# FPGA_PWR.net
KiCad netlist of a schematic drawn in Altium Designer
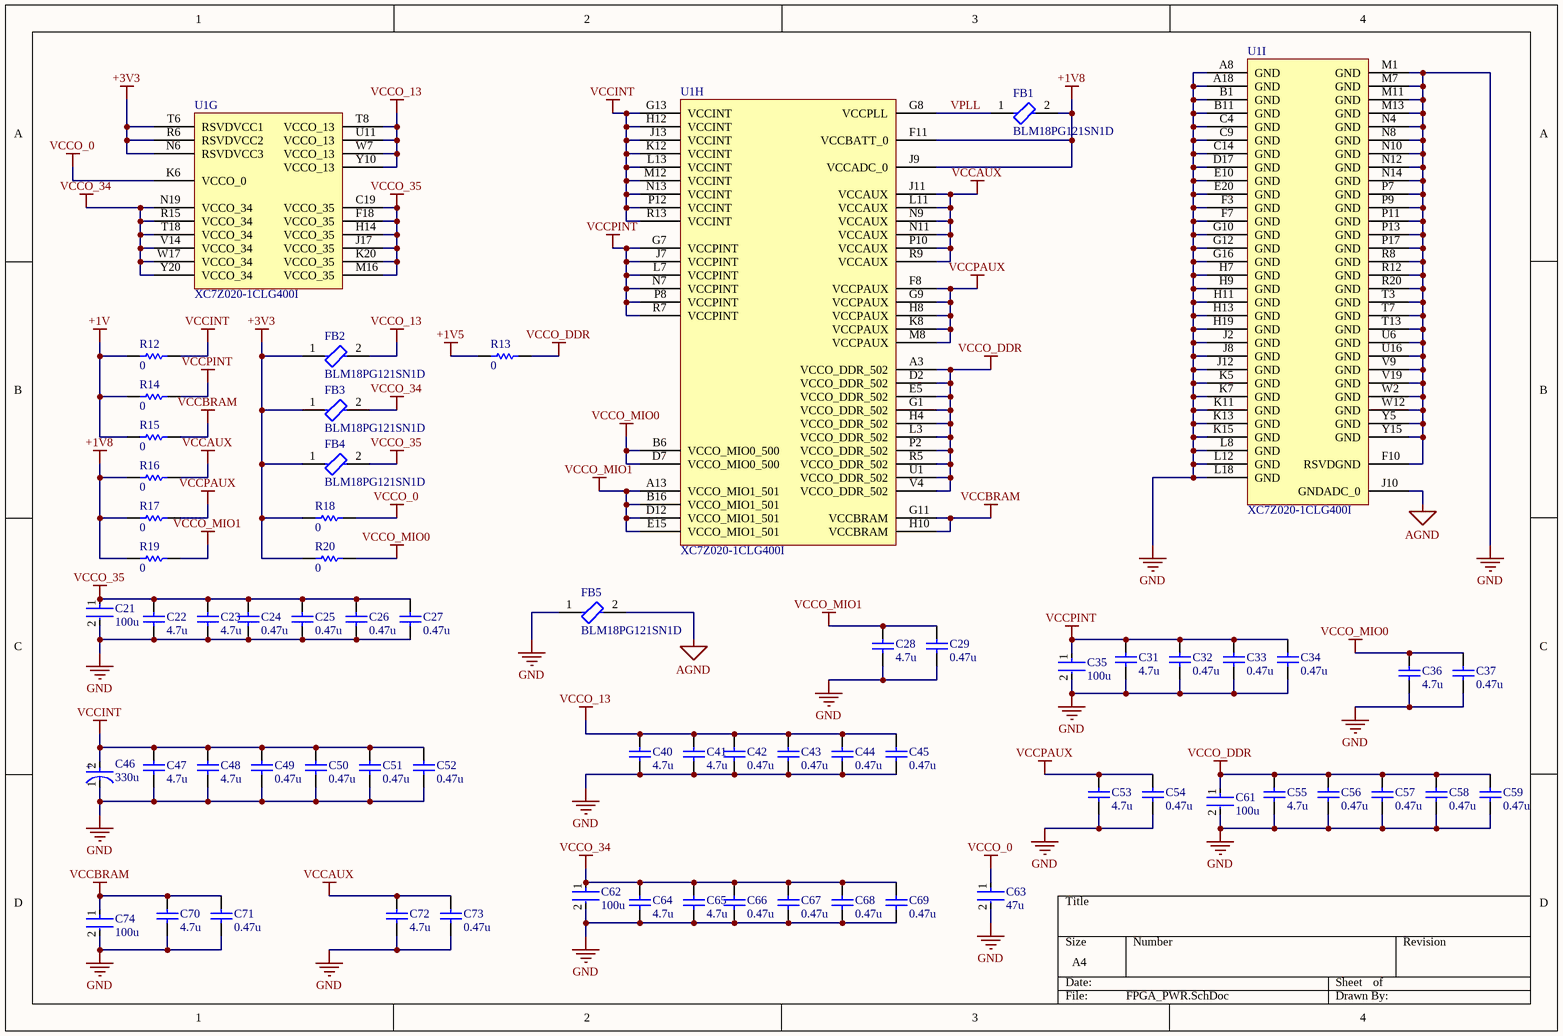
[diagram p0: FPGA_PWR.SchDoc]

(export (version "E")
  (design (tool "Eeschema 10.0.6"))
  (components
    (comp (ref "C21")
      (value "100u")
      (footprint "FP-GRM32E-0_3-0_2-MFG")
      (description "Chip Multilayer Ceramic Capacitors for General Purpose, 1210, 100uF, X7U, +22%/-56%, 20%, 4V")
      (fields (field (name "TOLERANCE") "20%"))
      (libsource (lib "Altium Content Vault") (part "02cd4be3c70576c341d710602a673aa"))
    )
    (comp (ref "C22")
      (value "4.7u")
      (footprint "CAPC2013X135X45LL10T25")
      (fields (field (name "MANUFACTURER") "Murata") (field (name "PART NUMBER") "GRM21BR71A475KA73L"))
      (libsource (lib "Altium Content Vault") (part "CAP"))
    )
    (comp (ref "C23")
      (value "4.7u")
      (footprint "CAPC2013X135X45LL10T25")
      (fields (field (name "MANUFACTURER") "Murata") (field (name "PART NUMBER") "GRM21BR71A475KA73L"))
      (libsource (lib "Altium Content Vault") (part "CAP"))
    )
    (comp (ref "C24")
      (value "0.47u")
      (footprint "CAPC1608X90X35LL10T15")
      (fields (field (name "PART NUMBER") "GRM188R70J474KA01D") (field (name "MANUFACTURER") "Murata"))
      (libsource (lib "Altium Content Vault") (part "CAP"))
    )
    (comp (ref "C25")
      (value "0.47u")
      (footprint "CAPC1608X90X35LL10T15")
      (fields (field (name "PART NUMBER") "GRM188R70J474KA01D") (field (name "MANUFACTURER") "Murata"))
      (libsource (lib "Altium Content Vault") (part "CAP"))
    )
    (comp (ref "C26")
      (value "0.47u")
      (footprint "CAPC1608X90X35LL10T15")
      (fields (field (name "PART NUMBER") "GRM188R70J474KA01D") (field (name "MANUFACTURER") "Murata"))
      (libsource (lib "Altium Content Vault") (part "CAP"))
    )
    (comp (ref "C27")
      (value "0.47u")
      (footprint "CAPC1608X90X35LL10T15")
      (fields (field (name "PART NUMBER") "GRM188R70J474KA01D") (field (name "MANUFACTURER") "Murata"))
      (libsource (lib "Altium Content Vault") (part "CAP"))
    )
    (comp (ref "C28")
      (value "4.7u")
      (footprint "CAPC2013X135X45LL10T25")
      (fields (field (name "MANUFACTURER") "Murata") (field (name "PART NUMBER") "GRM21BR71A475KA73L"))
      (libsource (lib "Altium Content Vault") (part "CAP"))
    )
    (comp (ref "C29")
      (value "0.47u")
      (footprint "CAPC1608X90X35LL10T15")
      (fields (field (name "PART NUMBER") "GRM188R70J474KA01D") (field (name "MANUFACTURER") "Murata"))
      (libsource (lib "Altium Content Vault") (part "CAP"))
    )
    (comp (ref "C31")
      (value "4.7u")
      (footprint "CAPC2013X135X45LL10T25")
      (fields (field (name "MANUFACTURER") "Murata") (field (name "PART NUMBER") "GRM21BR71A475KA73L"))
      (libsource (lib "Altium Content Vault") (part "CAP"))
    )
    (comp (ref "C32")
      (value "0.47u")
      (footprint "CAPC1608X90X35LL10T15")
      (fields (field (name "PART NUMBER") "GRM188R70J474KA01D") (field (name "MANUFACTURER") "Murata"))
      (libsource (lib "Altium Content Vault") (part "CAP"))
    )
    (comp (ref "C33")
      (value "0.47u")
      (footprint "CAPC1608X90X35LL10T15")
      (fields (field (name "PART NUMBER") "GRM188R70J474KA01D") (field (name "MANUFACTURER") "Murata"))
      (libsource (lib "Altium Content Vault") (part "CAP"))
    )
    (comp (ref "C34")
      (value "0.47u")
      (footprint "CAPC1608X90X35LL10T15")
      (fields (field (name "PART NUMBER") "GRM188R70J474KA01D") (field (name "MANUFACTURER") "Murata"))
      (libsource (lib "Altium Content Vault") (part "CAP"))
    )
    (comp (ref "C35")
      (value "100u")
      (footprint "FP-GRM32E-0_3-0_2-MFG")
      (description "Chip Multilayer Ceramic Capacitors for General Purpose, 1210, 100uF, X7U, +22%/-56%, 20%, 4V")
      (fields (field (name "TOLERANCE") "20%"))
      (libsource (lib "Altium Content Vault") (part "02cd4be3c70576c341d710602a673aa"))
    )
    (comp (ref "C36")
      (value "4.7u")
      (footprint "CAPC2013X135X45LL10T25")
      (fields (field (name "MANUFACTURER") "Murata") (field (name "PART NUMBER") "GRM21BR71A475KA73L"))
      (libsource (lib "Altium Content Vault") (part "CAP"))
    )
    (comp (ref "C37")
      (value "0.47u")
      (footprint "CAPC1608X90X35LL10T15")
      (fields (field (name "PART NUMBER") "GRM188R70J474KA01D") (field (name "MANUFACTURER") "Murata"))
      (libsource (lib "Altium Content Vault") (part "CAP"))
    )
    (comp (ref "C40")
      (value "4.7u")
      (footprint "CAPC2013X135X45LL10T25")
      (fields (field (name "MANUFACTURER") "Murata") (field (name "PART NUMBER") "GRM21BR71A475KA73L"))
      (libsource (lib "Altium Content Vault") (part "CAP"))
    )
    (comp (ref "C41")
      (value "4.7u")
      (footprint "CAPC2013X135X45LL10T25")
      (fields (field (name "MANUFACTURER") "Murata") (field (name "PART NUMBER") "GRM21BR71A475KA73L"))
      (libsource (lib "Altium Content Vault") (part "CAP"))
    )
    (comp (ref "C42")
      (value "0.47u")
      (footprint "CAPC1608X90X35LL10T15")
      (fields (field (name "PART NUMBER") "GRM188R70J474KA01D") (field (name "MANUFACTURER") "Murata"))
      (libsource (lib "Altium Content Vault") (part "CAP"))
    )
    (comp (ref "C43")
      (value "0.47u")
      (footprint "CAPC1608X90X35LL10T15")
      (fields (field (name "PART NUMBER") "GRM188R70J474KA01D") (field (name "MANUFACTURER") "Murata"))
      (libsource (lib "Altium Content Vault") (part "CAP"))
    )
    (comp (ref "C44")
      (value "0.47u")
      (footprint "CAPC1608X90X35LL10T15")
      (fields (field (name "PART NUMBER") "GRM188R70J474KA01D") (field (name "MANUFACTURER") "Murata"))
      (libsource (lib "Altium Content Vault") (part "CAP"))
    )
    (comp (ref "C45")
      (value "0.47u")
      (footprint "CAPC1608X90X35LL10T15")
      (fields (field (name "PART NUMBER") "GRM188R70J474KA01D") (field (name "MANUFACTURER") "Murata"))
      (libsource (lib "Altium Content Vault") (part "CAP"))
    )
    (comp (ref "C46")
      (value "330u")
      (footprint "FP-POSCAP-D2E-MFG")
      (description "Molded Tantalum Polymer Capacitor 330uF 20% 6.3V life 2000Hours SMD 2917")
      (fields (field (name "VOLTAGE") "6.3V") (field (name "TOLERANCE") "20%"))
      (libsource (lib "Altium Content Vault") (part "84cdeef69100fe67ea2095257d64e1a"))
    )
    (comp (ref "C47")
      (value "4.7u")
      (footprint "CAPC2013X135X45LL10T25")
      (fields (field (name "MANUFACTURER") "Murata") (field (name "PART NUMBER") "GRM21BR71A475KA73L"))
      (libsource (lib "Altium Content Vault") (part "CAP"))
    )
    (comp (ref "C48")
      (value "4.7u")
      (footprint "CAPC2013X135X45LL10T25")
      (fields (field (name "MANUFACTURER") "Murata") (field (name "PART NUMBER") "GRM21BR71A475KA73L"))
      (libsource (lib "Altium Content Vault") (part "CAP"))
    )
    (comp (ref "C49")
      (value "0.47u")
      (footprint "CAPC1608X90X35LL10T15")
      (fields (field (name "PART NUMBER") "GRM188R70J474KA01D") (field (name "MANUFACTURER") "Murata"))
      (libsource (lib "Altium Content Vault") (part "CAP"))
    )
    (comp (ref "C50")
      (value "0.47u")
      (footprint "CAPC1608X90X35LL10T15")
      (fields (field (name "PART NUMBER") "GRM188R70J474KA01D") (field (name "MANUFACTURER") "Murata"))
      (libsource (lib "Altium Content Vault") (part "CAP"))
    )
    (comp (ref "C51")
      (value "0.47u")
      (footprint "CAPC1608X90X35LL10T15")
      (fields (field (name "PART NUMBER") "GRM188R70J474KA01D") (field (name "MANUFACTURER") "Murata"))
      (libsource (lib "Altium Content Vault") (part "CAP"))
    )
    (comp (ref "C52")
      (value "0.47u")
      (footprint "CAPC1608X90X35LL10T15")
      (fields (field (name "PART NUMBER") "GRM188R70J474KA01D") (field (name "MANUFACTURER") "Murata"))
      (libsource (lib "Altium Content Vault") (part "CAP"))
    )
    (comp (ref "C53")
      (value "4.7u")
      (footprint "CAPC2013X135X45LL10T25")
      (fields (field (name "MANUFACTURER") "Murata") (field (name "PART NUMBER") "GRM21BR71A475KA73L"))
      (libsource (lib "Altium Content Vault") (part "CAP"))
    )
    (comp (ref "C54")
      (value "0.47u")
      (footprint "CAPC1608X90X35LL10T15")
      (fields (field (name "PART NUMBER") "GRM188R70J474KA01D") (field (name "MANUFACTURER") "Murata"))
      (libsource (lib "Altium Content Vault") (part "CAP"))
    )
    (comp (ref "C55")
      (value "4.7u")
      (footprint "CAPC2013X135X45LL10T25")
      (fields (field (name "MANUFACTURER") "Murata") (field (name "PART NUMBER") "GRM21BR71A475KA73L"))
      (libsource (lib "Altium Content Vault") (part "CAP"))
    )
    (comp (ref "C56")
      (value "0.47u")
      (footprint "CAPC1608X90X35LL10T15")
      (fields (field (name "PART NUMBER") "GRM188R70J474KA01D") (field (name "MANUFACTURER") "Murata"))
      (libsource (lib "Altium Content Vault") (part "CAP"))
    )
    (comp (ref "C57")
      (value "0.47u")
      (footprint "CAPC1608X90X35LL10T15")
      (fields (field (name "PART NUMBER") "GRM188R70J474KA01D") (field (name "MANUFACTURER") "Murata"))
      (libsource (lib "Altium Content Vault") (part "CAP"))
    )
    (comp (ref "C58")
      (value "0.47u")
      (footprint "CAPC1608X90X35LL10T15")
      (fields (field (name "PART NUMBER") "GRM188R70J474KA01D") (field (name "MANUFACTURER") "Murata"))
      (libsource (lib "Altium Content Vault") (part "CAP"))
    )
    (comp (ref "C59")
      (value "0.47u")
      (footprint "CAPC1608X90X35LL10T15")
      (fields (field (name "PART NUMBER") "GRM188R70J474KA01D") (field (name "MANUFACTURER") "Murata"))
      (libsource (lib "Altium Content Vault") (part "CAP"))
    )
    (comp (ref "C61")
      (value "100u")
      (footprint "FP-GRM32E-0_3-0_2-MFG")
      (description "Chip Multilayer Ceramic Capacitors for General Purpose, 1210, 100uF, X7U, +22%/-56%, 20%, 4V")
      (fields (field (name "TOLERANCE") "20%"))
      (libsource (lib "Altium Content Vault") (part "02cd4be3c70576c341d710602a673aa"))
    )
    (comp (ref "C62")
      (value "100u")
      (footprint "FP-GRM32E-0_3-0_2-MFG")
      (description "Chip Multilayer Ceramic Capacitors for General Purpose, 1210, 100uF, X7U, +22%/-56%, 20%, 4V")
      (fields (field (name "TOLERANCE") "20%"))
      (libsource (lib "Altium Content Vault") (part "02cd4be3c70576c341d710602a673aa"))
    )
    (comp (ref "C63")
      (value "47u")
      (footprint "FP-GRM32E-0_3-0_2-IPC_C")
      (description "Chip Multilayer Ceramic Capacitors for General Purpose, 1210, 47uF, X7R, 15%, 20%, 6.3V")
      (fields (field (name "TOLERANCE") "20%"))
      (libsource (lib "Altium Content Vault") (part "02cd4be3c70576c341d710602a673aa"))
    )
    (comp (ref "C64")
      (value "4.7u")
      (footprint "CAPC2013X135X45LL10T25")
      (fields (field (name "MANUFACTURER") "Murata") (field (name "PART NUMBER") "GRM21BR71A475KA73L"))
      (libsource (lib "Altium Content Vault") (part "CAP"))
    )
    (comp (ref "C65")
      (value "4.7u")
      (footprint "CAPC2013X135X45LL10T25")
      (fields (field (name "MANUFACTURER") "Murata") (field (name "PART NUMBER") "GRM21BR71A475KA73L"))
      (libsource (lib "Altium Content Vault") (part "CAP"))
    )
    (comp (ref "C66")
      (value "0.47u")
      (footprint "CAPC1608X90X35LL10T15")
      (fields (field (name "PART NUMBER") "GRM188R70J474KA01D") (field (name "MANUFACTURER") "Murata"))
      (libsource (lib "Altium Content Vault") (part "CAP"))
    )
    (comp (ref "C67")
      (value "0.47u")
      (footprint "CAPC1608X90X35LL10T15")
      (fields (field (name "PART NUMBER") "GRM188R70J474KA01D") (field (name "MANUFACTURER") "Murata"))
      (libsource (lib "Altium Content Vault") (part "CAP"))
    )
    (comp (ref "C68")
      (value "0.47u")
      (footprint "CAPC1608X90X35LL10T15")
      (fields (field (name "PART NUMBER") "GRM188R70J474KA01D") (field (name "MANUFACTURER") "Murata"))
      (libsource (lib "Altium Content Vault") (part "CAP"))
    )
    (comp (ref "C69")
      (value "0.47u")
      (footprint "CAPC1608X90X35LL10T15")
      (fields (field (name "PART NUMBER") "GRM188R70J474KA01D") (field (name "MANUFACTURER") "Murata"))
      (libsource (lib "Altium Content Vault") (part "CAP"))
    )
    (comp (ref "C70")
      (value "4.7u")
      (footprint "CAPC2013X135X45LL10T25")
      (fields (field (name "MANUFACTURER") "Murata") (field (name "PART NUMBER") "GRM21BR71A475KA73L"))
      (libsource (lib "Altium Content Vault") (part "CAP"))
    )
    (comp (ref "C71")
      (value "0.47u")
      (footprint "CAPC1608X90X35LL10T15")
      (fields (field (name "PART NUMBER") "GRM188R70J474KA01D") (field (name "MANUFACTURER") "Murata"))
      (libsource (lib "Altium Content Vault") (part "CAP"))
    )
    (comp (ref "C72")
      (value "4.7u")
      (footprint "CAPC2013X135X45LL10T25")
      (fields (field (name "MANUFACTURER") "Murata") (field (name "PART NUMBER") "GRM21BR71A475KA73L"))
      (libsource (lib "Altium Content Vault") (part "CAP"))
    )
    (comp (ref "C73")
      (value "0.47u")
      (footprint "CAPC1608X90X35LL10T15")
      (fields (field (name "PART NUMBER") "GRM188R70J474KA01D") (field (name "MANUFACTURER") "Murata"))
      (libsource (lib "Altium Content Vault") (part "CAP"))
    )
    (comp (ref "C74")
      (value "100u")
      (footprint "FP-GRM32E-0_3-0_2-MFG")
      (description "Chip Multilayer Ceramic Capacitors for General Purpose, 1210, 100uF, X7U, +22%/-56%, 20%, 4V")
      (fields (field (name "TOLERANCE") "20%"))
      (libsource (lib "Altium Content Vault") (part "02cd4be3c70576c341d710602a673aa"))
    )
    (comp (ref "FB1")
      (value "BLM18PG121SN1D")
      (footprint "FP-BLM18-0_15-t0_8-IPC_A")
      (description "Chip Ferrite Bead, 0603, 120Ω @ 100MHz, 0.05Ω, 25%, 2A")
      (fields (field (name "TOLERANCE") "25%"))
      (libsource (lib "Altium Content Vault") (part "5f30dd21d616792df468990f7003faa"))
    )
    (comp (ref "FB2")
      (value "BLM18PG121SN1D")
      (footprint "FP-BLM18-0_15-t0_8-IPC_A")
      (description "Chip Ferrite Bead, 0603, 120Ω @ 100MHz, 0.05Ω, 25%, 2A")
      (fields (field (name "TOLERANCE") "25%"))
      (libsource (lib "Altium Content Vault") (part "5f30dd21d616792df468990f7003faa"))
    )
    (comp (ref "FB3")
      (value "BLM18PG121SN1D")
      (footprint "FP-BLM18-0_15-t0_8-IPC_A")
      (description "Chip Ferrite Bead, 0603, 120Ω @ 100MHz, 0.05Ω, 25%, 2A")
      (fields (field (name "TOLERANCE") "25%"))
      (libsource (lib "Altium Content Vault") (part "5f30dd21d616792df468990f7003faa"))
    )
    (comp (ref "FB4")
      (value "BLM18PG121SN1D")
      (footprint "FP-BLM18-0_15-t0_8-IPC_A")
      (description "Chip Ferrite Bead, 0603, 120Ω @ 100MHz, 0.05Ω, 25%, 2A")
      (fields (field (name "TOLERANCE") "25%"))
      (libsource (lib "Altium Content Vault") (part "5f30dd21d616792df468990f7003faa"))
    )
    (comp (ref "FB5")
      (value "BLM18PG121SN1D")
      (footprint "FP-BLM18-0_15-t0_8-IPC_A")
      (description "Chip Ferrite Bead, 0603, 120Ω @ 100MHz, 0.05Ω, 25%, 2A")
      (fields (field (name "TOLERANCE") "25%"))
      (libsource (lib "Altium Content Vault") (part "5f30dd21d616792df468990f7003faa"))
    )
    (comp (ref "R12")
      (value "0")
      (footprint "RESC1608X55X25ML10T15")
      (description "Chip Resistor, 0 Ohm, +/- 5%, 0.1 W, -55 to 155 degC, 0603 (1608 Metric), RoHS, Tape and Reel")
      (fields (field (name "TOLERANCE") "5%") (field (name "MANUFACTURER") "Yageo"))
      (libsource (lib "Altium Content Vault") (part "RES-2"))
    )
    (comp (ref "R13")
      (value "0")
      (footprint "RESC1608X55X25ML10T15")
      (description "Chip Resistor, 0 Ohm, +/- 5%, 0.1 W, -55 to 155 degC, 0603 (1608 Metric), RoHS, Tape and Reel")
      (fields (field (name "TOLERANCE") "5%") (field (name "MANUFACTURER") "Yageo"))
      (libsource (lib "Altium Content Vault") (part "RES-2"))
    )
    (comp (ref "R14")
      (value "0")
      (footprint "RESC1608X55X25ML10T15")
      (description "Chip Resistor, 0 Ohm, +/- 5%, 0.1 W, -55 to 155 degC, 0603 (1608 Metric), RoHS, Tape and Reel")
      (fields (field (name "TOLERANCE") "5%") (field (name "MANUFACTURER") "Yageo"))
      (libsource (lib "Altium Content Vault") (part "RES-2"))
    )
    (comp (ref "R15")
      (value "0")
      (footprint "RESC1608X55X25ML10T15")
      (description "Chip Resistor, 0 Ohm, +/- 5%, 0.1 W, -55 to 155 degC, 0603 (1608 Metric), RoHS, Tape and Reel")
      (fields (field (name "TOLERANCE") "5%") (field (name "MANUFACTURER") "Yageo"))
      (libsource (lib "Altium Content Vault") (part "RES-2"))
    )
    (comp (ref "R16")
      (value "0")
      (footprint "RESC1608X55X25ML10T15")
      (description "Chip Resistor, 0 Ohm, +/- 5%, 0.1 W, -55 to 155 degC, 0603 (1608 Metric), RoHS, Tape and Reel")
      (fields (field (name "TOLERANCE") "5%") (field (name "MANUFACTURER") "Yageo"))
      (libsource (lib "Altium Content Vault") (part "RES-2"))
    )
    (comp (ref "R17")
      (value "0")
      (footprint "RESC1608X55X25ML10T15")
      (description "Chip Resistor, 0 Ohm, +/- 5%, 0.1 W, -55 to 155 degC, 0603 (1608 Metric), RoHS, Tape and Reel")
      (fields (field (name "TOLERANCE") "5%") (field (name "MANUFACTURER") "Yageo"))
      (libsource (lib "Altium Content Vault") (part "RES-2"))
    )
    (comp (ref "R18")
      (value "0")
      (footprint "RESC1608X55X25ML10T15")
      (description "Chip Resistor, 0 Ohm, +/- 5%, 0.1 W, -55 to 155 degC, 0603 (1608 Metric), RoHS, Tape and Reel")
      (fields (field (name "TOLERANCE") "5%") (field (name "MANUFACTURER") "Yageo"))
      (libsource (lib "Altium Content Vault") (part "RES-2"))
    )
    (comp (ref "R19")
      (value "0")
      (footprint "RESC1608X55X25ML10T15")
      (description "Chip Resistor, 0 Ohm, +/- 5%, 0.1 W, -55 to 155 degC, 0603 (1608 Metric), RoHS, Tape and Reel")
      (fields (field (name "TOLERANCE") "5%") (field (name "MANUFACTURER") "Yageo"))
      (libsource (lib "Altium Content Vault") (part "RES-2"))
    )
    (comp (ref "R20")
      (value "0")
      (footprint "RESC1608X55X25ML10T15")
      (description "Chip Resistor, 0 Ohm, +/- 5%, 0.1 W, -55 to 155 degC, 0603 (1608 Metric), RoHS, Tape and Reel")
      (fields (field (name "TOLERANCE") "5%") (field (name "MANUFACTURER") "Yageo"))
      (libsource (lib "Altium Content Vault") (part "RES-2"))
    )
    (comp (ref "U1")
      (value "XC7Z020-1CLG400I")
      (footprint "CLG400")
      (fields (field (name "GENERIC PART NUMBER") "XC7Z020"))
      (libsource (lib "Altium Content Vault") (part "XNLX-XC7Z020-CLG400"))
    )
  )
  (nets
    (net (code "1") (name "+1V") (class "Default")
      (node (ref "R12") (pin "2") (pinfunction "2_2") (pintype "passive"))
      (node (ref "R14") (pin "2") (pinfunction "2_2") (pintype "passive"))
      (node (ref "R15") (pin "2") (pinfunction "2_2") (pintype "passive"))
    )
    (net (code "2") (name "+1V5") (class "Default")
      (node (ref "R13") (pin "2") (pinfunction "2_2") (pintype "passive"))
    )
    (net (code "3") (name "+1V8") (class "Default")
      (node (ref "FB1") (pin "2") (pinfunction "2_2") (pintype "passive"))
      (node (ref "R16") (pin "2") (pinfunction "2_2") (pintype "passive"))
      (node (ref "R17") (pin "2") (pinfunction "2_2") (pintype "passive"))
      (node (ref "R19") (pin "2") (pinfunction "2_2") (pintype "passive"))
      (node (ref "U1") (pin "F11") (pinfunction "VCCBATT_0_F11") (pintype "power_in"))
      (node (ref "U1") (pin "J9") (pinfunction "VCCADC_0_J9") (pintype "power_in"))
    )
    (net (code "4") (name "+3V3") (class "Default")
      (node (ref "FB2") (pin "1") (pinfunction "1_1") (pintype "passive"))
      (node (ref "FB3") (pin "1") (pinfunction "1_1") (pintype "passive"))
      (node (ref "FB4") (pin "1") (pinfunction "1_1") (pintype "passive"))
      (node (ref "R18") (pin "2") (pinfunction "2_2") (pintype "passive"))
      (node (ref "R20") (pin "2") (pinfunction "2_2") (pintype "passive"))
      (node (ref "U1") (pin "N6") (pinfunction "RSVDVCC3_N6") (pintype "power_in"))
      (node (ref "U1") (pin "R6") (pinfunction "RSVDVCC2_R6") (pintype "power_in"))
      (node (ref "U1") (pin "T6") (pinfunction "RSVDVCC1_T6") (pintype "power_in"))
    )
    (net (code "5") (name "/VPLL") (class "Default")
      (node (ref "FB1") (pin "1") (pinfunction "1_1") (pintype "passive"))
      (node (ref "U1") (pin "G8") (pinfunction "VCCPLL_G8") (pintype "power_in"))
    )
    (net (code "6") (name "AGND") (class "Default")
      (node (ref "FB5") (pin "2") (pinfunction "2_2") (pintype "passive"))
      (node (ref "U1") (pin "J10") (pinfunction "GNDADC_0_J10") (pintype "power_in"))
    )
    (net (code "7") (name "GND") (class "Default")
      (node (ref "C21") (pin "2") (pinfunction "2_2") (pintype "passive"))
      (node (ref "C22") (pin "1") (pinfunction "1_1") (pintype "passive"))
      (node (ref "C23") (pin "1") (pinfunction "1_1") (pintype "passive"))
      (node (ref "C24") (pin "1") (pinfunction "1_1") (pintype "passive"))
      (node (ref "C25") (pin "1") (pinfunction "1_1") (pintype "passive"))
      (node (ref "C26") (pin "1") (pinfunction "1_1") (pintype "passive"))
      (node (ref "C27") (pin "1") (pinfunction "1_1") (pintype "passive"))
      (node (ref "C28") (pin "1") (pinfunction "1_1") (pintype "passive"))
      (node (ref "C29") (pin "1") (pinfunction "1_1") (pintype "passive"))
      (node (ref "C31") (pin "1") (pinfunction "1_1") (pintype "passive"))
      (node (ref "C32") (pin "1") (pinfunction "1_1") (pintype "passive"))
      (node (ref "C33") (pin "1") (pinfunction "1_1") (pintype "passive"))
      (node (ref "C34") (pin "1") (pinfunction "1_1") (pintype "passive"))
      (node (ref "C35") (pin "2") (pinfunction "2_2") (pintype "passive"))
      (node (ref "C36") (pin "1") (pinfunction "1_1") (pintype "passive"))
      (node (ref "C37") (pin "1") (pinfunction "1_1") (pintype "passive"))
      (node (ref "C40") (pin "1") (pinfunction "1_1") (pintype "passive"))
      (node (ref "C41") (pin "1") (pinfunction "1_1") (pintype "passive"))
      (node (ref "C42") (pin "1") (pinfunction "1_1") (pintype "passive"))
      (node (ref "C43") (pin "1") (pinfunction "1_1") (pintype "passive"))
      (node (ref "C44") (pin "1") (pinfunction "1_1") (pintype "passive"))
      (node (ref "C45") (pin "1") (pinfunction "1_1") (pintype "passive"))
      (node (ref "C46") (pin "1") (pinfunction "C_1") (pintype "passive"))
      (node (ref "C47") (pin "1") (pinfunction "1_1") (pintype "passive"))
      (node (ref "C48") (pin "1") (pinfunction "1_1") (pintype "passive"))
      (node (ref "C49") (pin "1") (pinfunction "1_1") (pintype "passive"))
      (node (ref "C50") (pin "1") (pinfunction "1_1") (pintype "passive"))
      (node (ref "C51") (pin "1") (pinfunction "1_1") (pintype "passive"))
      (node (ref "C52") (pin "1") (pinfunction "1_1") (pintype "passive"))
      (node (ref "C53") (pin "1") (pinfunction "1_1") (pintype "passive"))
      (node (ref "C54") (pin "1") (pinfunction "1_1") (pintype "passive"))
      (node (ref "C55") (pin "1") (pinfunction "1_1") (pintype "passive"))
      (node (ref "C56") (pin "1") (pinfunction "1_1") (pintype "passive"))
      (node (ref "C57") (pin "1") (pinfunction "1_1") (pintype "passive"))
      (node (ref "C58") (pin "1") (pinfunction "1_1") (pintype "passive"))
      (node (ref "C59") (pin "1") (pinfunction "1_1") (pintype "passive"))
      (node (ref "C61") (pin "2") (pinfunction "2_2") (pintype "passive"))
      (node (ref "C62") (pin "2") (pinfunction "2_2") (pintype "passive"))
      (node (ref "C63") (pin "2") (pinfunction "2_2") (pintype "passive"))
      (node (ref "C64") (pin "1") (pinfunction "1_1") (pintype "passive"))
      (node (ref "C65") (pin "1") (pinfunction "1_1") (pintype "passive"))
      (node (ref "C66") (pin "1") (pinfunction "1_1") (pintype "passive"))
      (node (ref "C67") (pin "1") (pinfunction "1_1") (pintype "passive"))
      (node (ref "C68") (pin "1") (pinfunction "1_1") (pintype "passive"))
      (node (ref "C69") (pin "1") (pinfunction "1_1") (pintype "passive"))
      (node (ref "C70") (pin "1") (pinfunction "1_1") (pintype "passive"))
      (node (ref "C71") (pin "1") (pinfunction "1_1") (pintype "passive"))
      (node (ref "C72") (pin "1") (pinfunction "1_1") (pintype "passive"))
      (node (ref "C73") (pin "1") (pinfunction "1_1") (pintype "passive"))
      (node (ref "C74") (pin "2") (pinfunction "2_2") (pintype "passive"))
      (node (ref "FB5") (pin "1") (pinfunction "1_1") (pintype "passive"))
      (node (ref "U1") (pin "A18") (pinfunction "GND_A18") (pintype "power_in"))
      (node (ref "U1") (pin "A8") (pinfunction "GND_A8") (pintype "power_in"))
      (node (ref "U1") (pin "B1") (pinfunction "GND_B1") (pintype "power_in"))
      (node (ref "U1") (pin "B11") (pinfunction "GND_B11") (pintype "power_in"))
      (node (ref "U1") (pin "C14") (pinfunction "GND_C14") (pintype "power_in"))
      (node (ref "U1") (pin "C4") (pinfunction "GND_C4") (pintype "power_in"))
      (node (ref "U1") (pin "C9") (pinfunction "GND_C9") (pintype "power_in"))
      (node (ref "U1") (pin "D17") (pinfunction "GND_D17") (pintype "power_in"))
      (node (ref "U1") (pin "E10") (pinfunction "GND_E10") (pintype "power_in"))
      (node (ref "U1") (pin "E20") (pinfunction "GND_E20") (pintype "power_in"))
      (node (ref "U1") (pin "F10") (pinfunction "RSVDGND_F10") (pintype "power_in"))
      (node (ref "U1") (pin "F3") (pinfunction "GND_F3") (pintype "power_in"))
      (node (ref "U1") (pin "F7") (pinfunction "GND_F7") (pintype "power_in"))
      (node (ref "U1") (pin "G10") (pinfunction "GND_G10") (pintype "power_in"))
      (node (ref "U1") (pin "G12") (pinfunction "GND_G12") (pintype "power_in"))
      (node (ref "U1") (pin "G16") (pinfunction "GND_G16") (pintype "power_in"))
      (node (ref "U1") (pin "H11") (pinfunction "GND_H11") (pintype "power_in"))
      (node (ref "U1") (pin "H13") (pinfunction "GND_H13") (pintype "power_in"))
      (node (ref "U1") (pin "H19") (pinfunction "GND_H19") (pintype "power_in"))
      (node (ref "U1") (pin "H7") (pinfunction "GND_H7") (pintype "power_in"))
      (node (ref "U1") (pin "H9") (pinfunction "GND_H9") (pintype "power_in"))
      (node (ref "U1") (pin "J12") (pinfunction "GND_J12") (pintype "power_in"))
      (node (ref "U1") (pin "J2") (pinfunction "GND_J2") (pintype "power_in"))
      (node (ref "U1") (pin "J8") (pinfunction "GND_J8") (pintype "power_in"))
      (node (ref "U1") (pin "K11") (pinfunction "GND_K11") (pintype "power_in"))
      (node (ref "U1") (pin "K13") (pinfunction "GND_K13") (pintype "power_in"))
      (node (ref "U1") (pin "K15") (pinfunction "GND_K15") (pintype "power_in"))
      (node (ref "U1") (pin "K5") (pinfunction "GND_K5") (pintype "power_in"))
      (node (ref "U1") (pin "K7") (pinfunction "GND_K7") (pintype "power_in"))
      (node (ref "U1") (pin "L12") (pinfunction "GND_L12") (pintype "power_in"))
      (node (ref "U1") (pin "L18") (pinfunction "GND_L18") (pintype "power_in"))
      (node (ref "U1") (pin "L8") (pinfunction "GND_L8") (pintype "power_in"))
      (node (ref "U1") (pin "M1") (pinfunction "GND_M1") (pintype "power_in"))
      (node (ref "U1") (pin "M11") (pinfunction "GND_M11") (pintype "power_in"))
      (node (ref "U1") (pin "M13") (pinfunction "GND_M13") (pintype "power_in"))
      (node (ref "U1") (pin "M7") (pinfunction "GND_M7") (pintype "power_in"))
      (node (ref "U1") (pin "N10") (pinfunction "GND_N10") (pintype "power_in"))
      (node (ref "U1") (pin "N12") (pinfunction "GND_N12") (pintype "power_in"))
      (node (ref "U1") (pin "N14") (pinfunction "GND_N14") (pintype "power_in"))
      (node (ref "U1") (pin "N4") (pinfunction "GND_N4") (pintype "power_in"))
      (node (ref "U1") (pin "N8") (pinfunction "GND_N8") (pintype "power_in"))
      (node (ref "U1") (pin "P11") (pinfunction "GND_P11") (pintype "power_in"))
      (node (ref "U1") (pin "P13") (pinfunction "GND_P13") (pintype "power_in"))
      (node (ref "U1") (pin "P17") (pinfunction "GND_P17") (pintype "power_in"))
      (node (ref "U1") (pin "P7") (pinfunction "GND_P7") (pintype "power_in"))
      (node (ref "U1") (pin "P9") (pinfunction "GND_P9") (pintype "power_in"))
      (node (ref "U1") (pin "R12") (pinfunction "GND_R12") (pintype "power_in"))
      (node (ref "U1") (pin "R20") (pinfunction "GND_R20") (pintype "power_in"))
      (node (ref "U1") (pin "R8") (pinfunction "GND_R8") (pintype "power_in"))
      (node (ref "U1") (pin "T13") (pinfunction "GND_T13") (pintype "power_in"))
      (node (ref "U1") (pin "T3") (pinfunction "GND_T3") (pintype "power_in"))
      (node (ref "U1") (pin "T7") (pinfunction "GND_T7") (pintype "power_in"))
      (node (ref "U1") (pin "U16") (pinfunction "GND_U16") (pintype "power_in"))
      (node (ref "U1") (pin "U6") (pinfunction "GND_U6") (pintype "power_in"))
      (node (ref "U1") (pin "V19") (pinfunction "GND_V19") (pintype "power_in"))
      (node (ref "U1") (pin "V9") (pinfunction "GND_V9") (pintype "power_in"))
      (node (ref "U1") (pin "W12") (pinfunction "GND_W12") (pintype "power_in"))
      (node (ref "U1") (pin "W2") (pinfunction "GND_W2") (pintype "power_in"))
      (node (ref "U1") (pin "Y15") (pinfunction "GND_Y15") (pintype "power_in"))
      (node (ref "U1") (pin "Y5") (pinfunction "GND_Y5") (pintype "power_in"))
    )
    (net (code "8") (name "VCCAUX") (class "Default")
      (node (ref "C72") (pin "2") (pinfunction "2_2") (pintype "passive"))
      (node (ref "C73") (pin "2") (pinfunction "2_2") (pintype "passive"))
      (node (ref "R16") (pin "1") (pinfunction "1_1") (pintype "passive"))
      (node (ref "U1") (pin "J11") (pinfunction "VCCAUX_J11") (pintype "power_in"))
      (node (ref "U1") (pin "L11") (pinfunction "VCCAUX_L11") (pintype "power_in"))
      (node (ref "U1") (pin "N11") (pinfunction "VCCAUX_N11") (pintype "power_in"))
      (node (ref "U1") (pin "N9") (pinfunction "VCCAUX_N9") (pintype "power_in"))
      (node (ref "U1") (pin "P10") (pinfunction "VCCAUX_P10") (pintype "power_in"))
      (node (ref "U1") (pin "R9") (pinfunction "VCCAUX_R9") (pintype "power_in"))
    )
    (net (code "9") (name "VCCBRAM") (class "Default")
      (node (ref "C70") (pin "2") (pinfunction "2_2") (pintype "passive"))
      (node (ref "C71") (pin "2") (pinfunction "2_2") (pintype "passive"))
      (node (ref "C74") (pin "1") (pinfunction "1_1") (pintype "passive"))
      (node (ref "R15") (pin "1") (pinfunction "1_1") (pintype "passive"))
      (node (ref "U1") (pin "G11") (pinfunction "VCCBRAM_G11") (pintype "power_in"))
      (node (ref "U1") (pin "H10") (pinfunction "VCCBRAM_H10") (pintype "power_in"))
    )
    (net (code "10") (name "VCCINT") (class "Default")
      (node (ref "C46") (pin "2") (pinfunction "A_2") (pintype "passive"))
      (node (ref "C47") (pin "2") (pinfunction "2_2") (pintype "passive"))
      (node (ref "C48") (pin "2") (pinfunction "2_2") (pintype "passive"))
      (node (ref "C49") (pin "2") (pinfunction "2_2") (pintype "passive"))
      (node (ref "C50") (pin "2") (pinfunction "2_2") (pintype "passive"))
      (node (ref "C51") (pin "2") (pinfunction "2_2") (pintype "passive"))
      (node (ref "C52") (pin "2") (pinfunction "2_2") (pintype "passive"))
      (node (ref "R12") (pin "1") (pinfunction "1_1") (pintype "passive"))
      (node (ref "U1") (pin "G13") (pinfunction "VCCINT_G13") (pintype "power_in"))
      (node (ref "U1") (pin "H12") (pinfunction "VCCINT_H12") (pintype "power_in"))
      (node (ref "U1") (pin "J13") (pinfunction "VCCINT_J13") (pintype "power_in"))
      (node (ref "U1") (pin "K12") (pinfunction "VCCINT_K12") (pintype "power_in"))
      (node (ref "U1") (pin "L13") (pinfunction "VCCINT_L13") (pintype "power_in"))
      (node (ref "U1") (pin "M12") (pinfunction "VCCINT_M12") (pintype "power_in"))
      (node (ref "U1") (pin "N13") (pinfunction "VCCINT_N13") (pintype "power_in"))
      (node (ref "U1") (pin "P12") (pinfunction "VCCINT_P12") (pintype "power_in"))
      (node (ref "U1") (pin "R13") (pinfunction "VCCINT_R13") (pintype "power_in"))
    )
    (net (code "11") (name "VCCO_0") (class "Default")
      (node (ref "C63") (pin "1") (pinfunction "1_1") (pintype "passive"))
      (node (ref "R18") (pin "1") (pinfunction "1_1") (pintype "passive"))
      (node (ref "U1") (pin "K6") (pinfunction "VCCO_0_K6") (pintype "power_in"))
    )
    (net (code "12") (name "VCCO_13") (class "Default")
      (node (ref "C40") (pin "2") (pinfunction "2_2") (pintype "passive"))
      (node (ref "C41") (pin "2") (pinfunction "2_2") (pintype "passive"))
      (node (ref "C42") (pin "2") (pinfunction "2_2") (pintype "passive"))
      (node (ref "C43") (pin "2") (pinfunction "2_2") (pintype "passive"))
      (node (ref "C44") (pin "2") (pinfunction "2_2") (pintype "passive"))
      (node (ref "C45") (pin "2") (pinfunction "2_2") (pintype "passive"))
      (node (ref "FB2") (pin "2") (pinfunction "2_2") (pintype "passive"))
      (node (ref "U1") (pin "T8") (pinfunction "VCCO_13_T8") (pintype "power_in"))
      (node (ref "U1") (pin "U11") (pinfunction "VCCO_13_U11") (pintype "power_in"))
      (node (ref "U1") (pin "W7") (pinfunction "VCCO_13_W7") (pintype "power_in"))
      (node (ref "U1") (pin "Y10") (pinfunction "VCCO_13_Y10") (pintype "power_in"))
    )
    (net (code "13") (name "VCCO_34") (class "Default")
      (node (ref "C62") (pin "1") (pinfunction "1_1") (pintype "passive"))
      (node (ref "C64") (pin "2") (pinfunction "2_2") (pintype "passive"))
      (node (ref "C65") (pin "2") (pinfunction "2_2") (pintype "passive"))
      (node (ref "C66") (pin "2") (pinfunction "2_2") (pintype "passive"))
      (node (ref "C67") (pin "2") (pinfunction "2_2") (pintype "passive"))
      (node (ref "C68") (pin "2") (pinfunction "2_2") (pintype "passive"))
      (node (ref "C69") (pin "2") (pinfunction "2_2") (pintype "passive"))
      (node (ref "FB3") (pin "2") (pinfunction "2_2") (pintype "passive"))
      (node (ref "U1") (pin "N19") (pinfunction "VCCO_34_N19") (pintype "power_in"))
      (node (ref "U1") (pin "R15") (pinfunction "VCCO_34_R15") (pintype "power_in"))
      (node (ref "U1") (pin "T18") (pinfunction "VCCO_34_T18") (pintype "power_in"))
      (node (ref "U1") (pin "V14") (pinfunction "VCCO_34_V14") (pintype "power_in"))
      (node (ref "U1") (pin "W17") (pinfunction "VCCO_34_W17") (pintype "power_in"))
      (node (ref "U1") (pin "Y20") (pinfunction "VCCO_34_Y20") (pintype "power_in"))
    )
    (net (code "14") (name "VCCO_35") (class "Default")
      (node (ref "C21") (pin "1") (pinfunction "1_1") (pintype "passive"))
      (node (ref "C22") (pin "2") (pinfunction "2_2") (pintype "passive"))
      (node (ref "C23") (pin "2") (pinfunction "2_2") (pintype "passive"))
      (node (ref "C24") (pin "2") (pinfunction "2_2") (pintype "passive"))
      (node (ref "C25") (pin "2") (pinfunction "2_2") (pintype "passive"))
      (node (ref "C26") (pin "2") (pinfunction "2_2") (pintype "passive"))
      (node (ref "C27") (pin "2") (pinfunction "2_2") (pintype "passive"))
      (node (ref "FB4") (pin "2") (pinfunction "2_2") (pintype "passive"))
      (node (ref "U1") (pin "C19") (pinfunction "VCCO_35_C19") (pintype "power_in"))
      (node (ref "U1") (pin "F18") (pinfunction "VCCO_35_F18") (pintype "power_in"))
      (node (ref "U1") (pin "H14") (pinfunction "VCCO_35_H14") (pintype "power_in"))
      (node (ref "U1") (pin "J17") (pinfunction "VCCO_35_J17") (pintype "power_in"))
      (node (ref "U1") (pin "K20") (pinfunction "VCCO_35_K20") (pintype "power_in"))
      (node (ref "U1") (pin "M16") (pinfunction "VCCO_35_M16") (pintype "power_in"))
    )
    (net (code "15") (name "VCCO_DDR") (class "Default")
      (node (ref "C55") (pin "2") (pinfunction "2_2") (pintype "passive"))
      (node (ref "C56") (pin "2") (pinfunction "2_2") (pintype "passive"))
      (node (ref "C57") (pin "2") (pinfunction "2_2") (pintype "passive"))
      (node (ref "C58") (pin "2") (pinfunction "2_2") (pintype "passive"))
      (node (ref "C59") (pin "2") (pinfunction "2_2") (pintype "passive"))
      (node (ref "C61") (pin "1") (pinfunction "1_1") (pintype "passive"))
      (node (ref "R13") (pin "1") (pinfunction "1_1") (pintype "passive"))
      (node (ref "U1") (pin "A3") (pinfunction "VCCO_DDR_502_A3") (pintype "power_in"))
      (node (ref "U1") (pin "D2") (pinfunction "VCCO_DDR_502_D2") (pintype "power_in"))
      (node (ref "U1") (pin "E5") (pinfunction "VCCO_DDR_502_E5") (pintype "power_in"))
      (node (ref "U1") (pin "G1") (pinfunction "VCCO_DDR_502_G1") (pintype "power_in"))
      (node (ref "U1") (pin "H4") (pinfunction "VCCO_DDR_502_H4") (pintype "power_in"))
      (node (ref "U1") (pin "L3") (pinfunction "VCCO_DDR_502_L3") (pintype "power_in"))
      (node (ref "U1") (pin "P2") (pinfunction "VCCO_DDR_502_P2") (pintype "power_in"))
      (node (ref "U1") (pin "R5") (pinfunction "VCCO_DDR_502_R5") (pintype "power_in"))
      (node (ref "U1") (pin "U1") (pinfunction "VCCO_DDR_502_U1") (pintype "power_in"))
      (node (ref "U1") (pin "V4") (pinfunction "VCCO_DDR_502_V4") (pintype "power_in"))
    )
    (net (code "16") (name "VCCO_MIO0") (class "Default")
      (node (ref "C36") (pin "2") (pinfunction "2_2") (pintype "passive"))
      (node (ref "C37") (pin "2") (pinfunction "2_2") (pintype "passive"))
      (node (ref "R20") (pin "1") (pinfunction "1_1") (pintype "passive"))
      (node (ref "U1") (pin "B6") (pinfunction "VCCO_MIO0_500_B6") (pintype "power_in"))
      (node (ref "U1") (pin "D7") (pinfunction "VCCO_MIO0_500_D7") (pintype "power_in"))
    )
    (net (code "17") (name "VCCO_MIO1") (class "Default")
      (node (ref "C28") (pin "2") (pinfunction "2_2") (pintype "passive"))
      (node (ref "C29") (pin "2") (pinfunction "2_2") (pintype "passive"))
      (node (ref "R19") (pin "1") (pinfunction "1_1") (pintype "passive"))
      (node (ref "U1") (pin "A13") (pinfunction "VCCO_MIO1_501_A13") (pintype "power_in"))
      (node (ref "U1") (pin "B16") (pinfunction "VCCO_MIO1_501_B16") (pintype "power_in"))
      (node (ref "U1") (pin "D12") (pinfunction "VCCO_MIO1_501_D12") (pintype "power_in"))
      (node (ref "U1") (pin "E15") (pinfunction "VCCO_MIO1_501_E15") (pintype "power_in"))
    )
    (net (code "18") (name "VCCPAUX") (class "Default")
      (node (ref "C53") (pin "2") (pinfunction "2_2") (pintype "passive"))
      (node (ref "C54") (pin "2") (pinfunction "2_2") (pintype "passive"))
      (node (ref "R17") (pin "1") (pinfunction "1_1") (pintype "passive"))
      (node (ref "U1") (pin "F8") (pinfunction "VCCPAUX_F8") (pintype "power_in"))
      (node (ref "U1") (pin "G9") (pinfunction "VCCPAUX_G9") (pintype "power_in"))
      (node (ref "U1") (pin "H8") (pinfunction "VCCPAUX_H8") (pintype "power_in"))
      (node (ref "U1") (pin "K8") (pinfunction "VCCPAUX_K8") (pintype "power_in"))
      (node (ref "U1") (pin "M8") (pinfunction "VCCPAUX_M8") (pintype "power_in"))
    )
    (net (code "19") (name "VCCPINT") (class "Default")
      (node (ref "C31") (pin "2") (pinfunction "2_2") (pintype "passive"))
      (node (ref "C32") (pin "2") (pinfunction "2_2") (pintype "passive"))
      (node (ref "C33") (pin "2") (pinfunction "2_2") (pintype "passive"))
      (node (ref "C34") (pin "2") (pinfunction "2_2") (pintype "passive"))
      (node (ref "C35") (pin "1") (pinfunction "1_1") (pintype "passive"))
      (node (ref "R14") (pin "1") (pinfunction "1_1") (pintype "passive"))
      (node (ref "U1") (pin "G7") (pinfunction "VCCPINT_G7") (pintype "power_in"))
      (node (ref "U1") (pin "J7") (pinfunction "VCCPINT_J7") (pintype "power_in"))
      (node (ref "U1") (pin "L7") (pinfunction "VCCPINT_L7") (pintype "power_in"))
      (node (ref "U1") (pin "N7") (pinfunction "VCCPINT_N7") (pintype "power_in"))
      (node (ref "U1") (pin "P8") (pinfunction "VCCPINT_P8") (pintype "power_in"))
      (node (ref "U1") (pin "R7") (pinfunction "VCCPINT_R7") (pintype "power_in"))
    )
  )
)
